# Relay_Module.net
KiCad netlist of a schematic drawn in Altium Designer
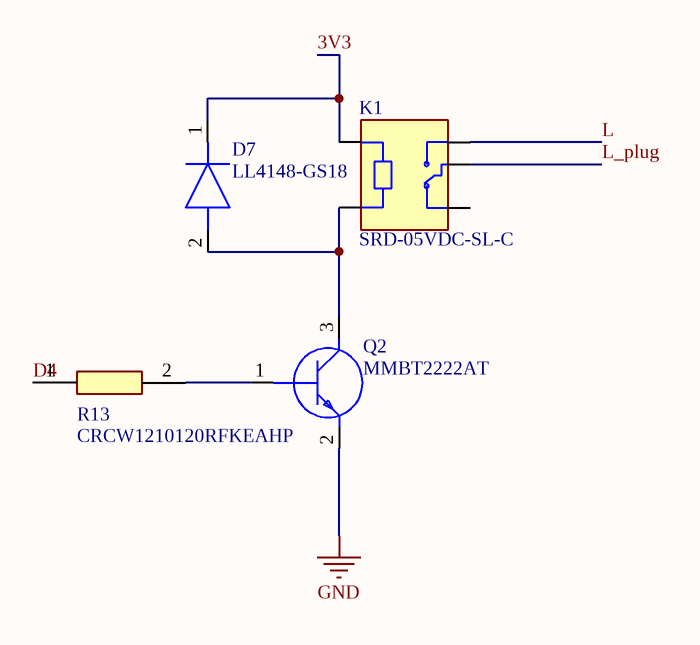
[diagram p0: Relay Module.SchDoc]

(export (version "E")
  (design (tool "Eeschema 10.0.6"))
  (components
    (comp (ref "D7")
      (value "LL4148-GS18")
      (footprint "SamacSys:SOD-80")
      (description "Diode")
      (fields (field (name "MOUSER PART NUMBER") "78-LL4148-GS18"))
      (libsource (lib "*") (part "LL4148-GS18"))
    )
    (comp (ref "K1")
      (value "SRD-05VDC-SL-C")
      (footprint "RELAY_SRD-05VDC-SL-C")
      (fields (field (name "MF") "Songle Relay"))
      (libsource (lib "SRD-05VDC-SL-C") (part "SRD-05VDC-SL-C"))
    )
    (comp (ref "Q2")
      (value "MMBT2222AT")
      (footprint "SamacSys:SOTFL50P160X78-3N")
      (description "Transistor BJT NPN")
      (fields (field (name "MOUSER PART NUMBER") "512-MMBT2222AT"))
      (libsource (lib "*") (part "MMBT2222AT"))
    )
    (comp (ref "R13")
      (value "CRCW1210120RFKEAHP")
      (footprint "SamacSys:RESC3225X70N")
      (description "Resistor")
      (fields (field (name "MOUSER PART NUMBER") "71-CRCW1210120RFKEAH"))
      (libsource (lib "*") (part "CRCW1210120RFKEAHP"))
    )
  )
  (nets
    (net (code "1") (name "/3V3") (class "Default")
      (node (ref "D7") (pin "1") (pinfunction "K_1") (pintype "passive"))
      (node (ref "K1") (pin "A1") (pinfunction "A1_A1") (pintype "passive"))
    )
    (net (code "2") (name "/D4") (class "Default")
      (node (ref "R13") (pin "1") (pinfunction "1_1") (pintype "passive"))
    )
    (net (code "3") (name "/L") (class "Default")
      (node (ref "K1") (pin "NO") (pinfunction "NO_NO") (pintype "passive"))
    )
    (net (code "4") (name "/L_plug") (class "Default")
      (node (ref "K1") (pin "COM") (pinfunction "COM_COM") (pintype "passive"))
    )
    (net (code "5") (name "GND") (class "Default")
      (node (ref "Q2") (pin "2") (pinfunction "E_2") (pintype "passive"))
    )
    (net (code "6") (name "Net-(D7-A)") (class "Default")
      (node (ref "D7") (pin "2") (pinfunction "A_2") (pintype "passive"))
      (node (ref "K1") (pin "A2") (pinfunction "A2_A2") (pintype "passive"))
      (node (ref "Q2") (pin "3") (pinfunction "C_3") (pintype "passive"))
    )
    (net (code "7") (name "Net-(Q2-B)") (class "Default")
      (node (ref "Q2") (pin "1") (pinfunction "B_1") (pintype "passive"))
      (node (ref "R13") (pin "2") (pinfunction "2_2") (pintype "passive"))
    )
    (net (code "8") (name "unconnected-(K1-PadNC)") (class "Default")
      (node (ref "K1") (pin "NC") (pinfunction "NC_NC") (pintype "passive"))
    )
  )
)
